# 2002_RTC.net
KiCad netlist of a schematic drawn in Altium Designer
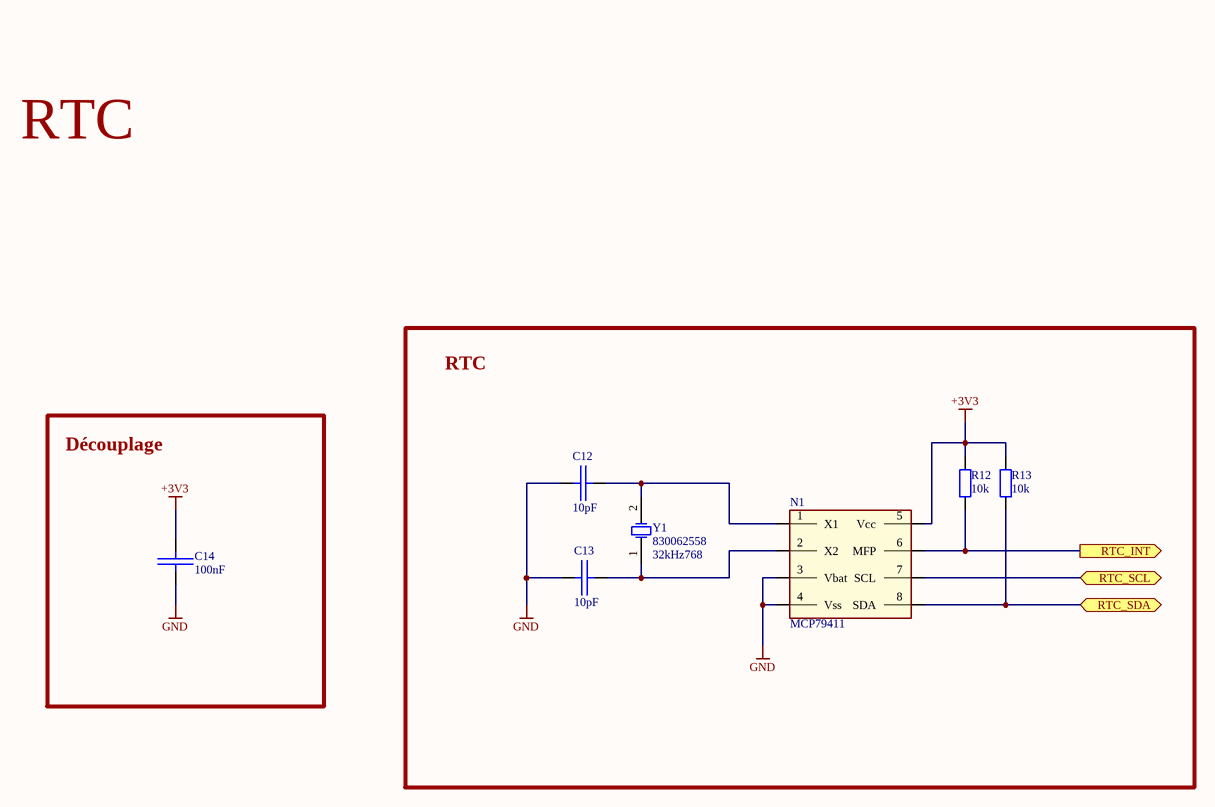
[diagram p0: 2002_RTC.SchDoc]

(export (version "E")
  (design (tool "Eeschema 10.0.6"))
  (components
    (comp (ref "C12")
      (value "10pF")
      (footprint "0805")
      (description "0805 Condensator")
      (libsource (lib "2002_CapteurMeteoWifi") (part "Condensator"))
    )
    (comp (ref "C13")
      (value "10pF")
      (footprint "0805")
      (description "0805 Condensator")
      (libsource (lib "2002_CapteurMeteoWifi") (part "Condensator"))
    )
    (comp (ref "C14")
      (value "100nF")
      (footprint "0805")
      (description "0805 Condensator")
      (libsource (lib "2002_CapteurMeteoWifi") (part "Condensator"))
    )
    (comp (ref "N1")
      (value "MCP79411")
      (footprint "MCP79411")
      (description "RTC")
      (libsource (lib "Schlib1") (part "MCP79411"))
    )
    (comp (ref "R12")
      (value "10k")
      (footprint "0805")
      (description "SMD Resistor")
      (fields (field (name "PART NUMBER") "ERJ6ENF2703V") (field (name "MANUFACTURER") "Panasonic"))
      (libsource (lib "2121_Robot3roues_V2.0") (part "RES"))
    )
    (comp (ref "R13")
      (value "10k")
      (footprint "0805")
      (description "SMD Resistor")
      (fields (field (name "PART NUMBER") "ERJ6ENF2703V") (field (name "MANUFACTURER") "Panasonic"))
      (libsource (lib "2121_Robot3roues_V2.0") (part "RES"))
    )
    (comp (ref "Y1")
      (value "830062558")
      (footprint "WE-XTAL_IQXC-25")
      (description "Crystals WE-XTAL 32.7680kHz 20ppm 2.0 x 1.2mm")
      (fields
        (field (name "MANUFACTURER PART NUMBER") "830020423")
        (field (name "MANUFACTURER") "Wurth Elektronik")
        (field (name "FREQUENCY") "32kHz768")
      )
      (libsource (lib "WE-XTAL") (part "830020423"))
    )
  )
  (nets
    (net (code "1") (name "+3V3") (class "Default")
      (node (ref "C14") (pin "1") (pinfunction "1_1") (pintype "passive"))
      (node (ref "N1") (pin "5") (pinfunction "Vcc_5") (pintype "passive"))
      (node (ref "R12") (pin "1") (pinfunction "1_1") (pintype "passive"))
      (node (ref "R13") (pin "1") (pinfunction "1_1") (pintype "passive"))
    )
    (net (code "2") (name "/RTC_INT") (class "Default")
      (node (ref "N1") (pin "6") (pinfunction "MFP_6") (pintype "passive"))
      (node (ref "R12") (pin "2") (pinfunction "2_2") (pintype "passive"))
    )
    (net (code "3") (name "/RTC_SCL") (class "Default")
      (node (ref "N1") (pin "7") (pinfunction "SCL_7") (pintype "passive"))
    )
    (net (code "4") (name "/RTC_SDA") (class "Default")
      (node (ref "N1") (pin "8") (pinfunction "SDA_8") (pintype "passive"))
      (node (ref "R13") (pin "2") (pinfunction "2_2") (pintype "passive"))
    )
    (net (code "5") (name "GND") (class "Default")
      (node (ref "C12") (pin "1") (pinfunction "1_1") (pintype "passive"))
      (node (ref "C13") (pin "1") (pinfunction "1_1") (pintype "passive"))
      (node (ref "C14") (pin "2") (pinfunction "2_2") (pintype "passive"))
      (node (ref "N1") (pin "3") (pinfunction "Vbat_3") (pintype "passive"))
      (node (ref "N1") (pin "4") (pinfunction "Vss_4") (pintype "passive"))
    )
    (net (code "6") (name "Net-(N1-X1)") (class "Default")
      (node (ref "C12") (pin "2") (pinfunction "2_2") (pintype "passive"))
      (node (ref "N1") (pin "1") (pinfunction "X1_1") (pintype "passive"))
      (node (ref "Y1") (pin "2") (pinfunction "OSC2_2") (pintype "passive"))
    )
    (net (code "7") (name "Net-(N1-X2)") (class "Default")
      (node (ref "C13") (pin "2") (pinfunction "2_2") (pintype "passive"))
      (node (ref "N1") (pin "2") (pinfunction "X2_2") (pintype "passive"))
      (node (ref "Y1") (pin "1") (pinfunction "OSC1_1") (pintype "passive"))
    )
  )
)
